# Charge_Controller.net
KiCad netlist of a schematic drawn in Altium Designer
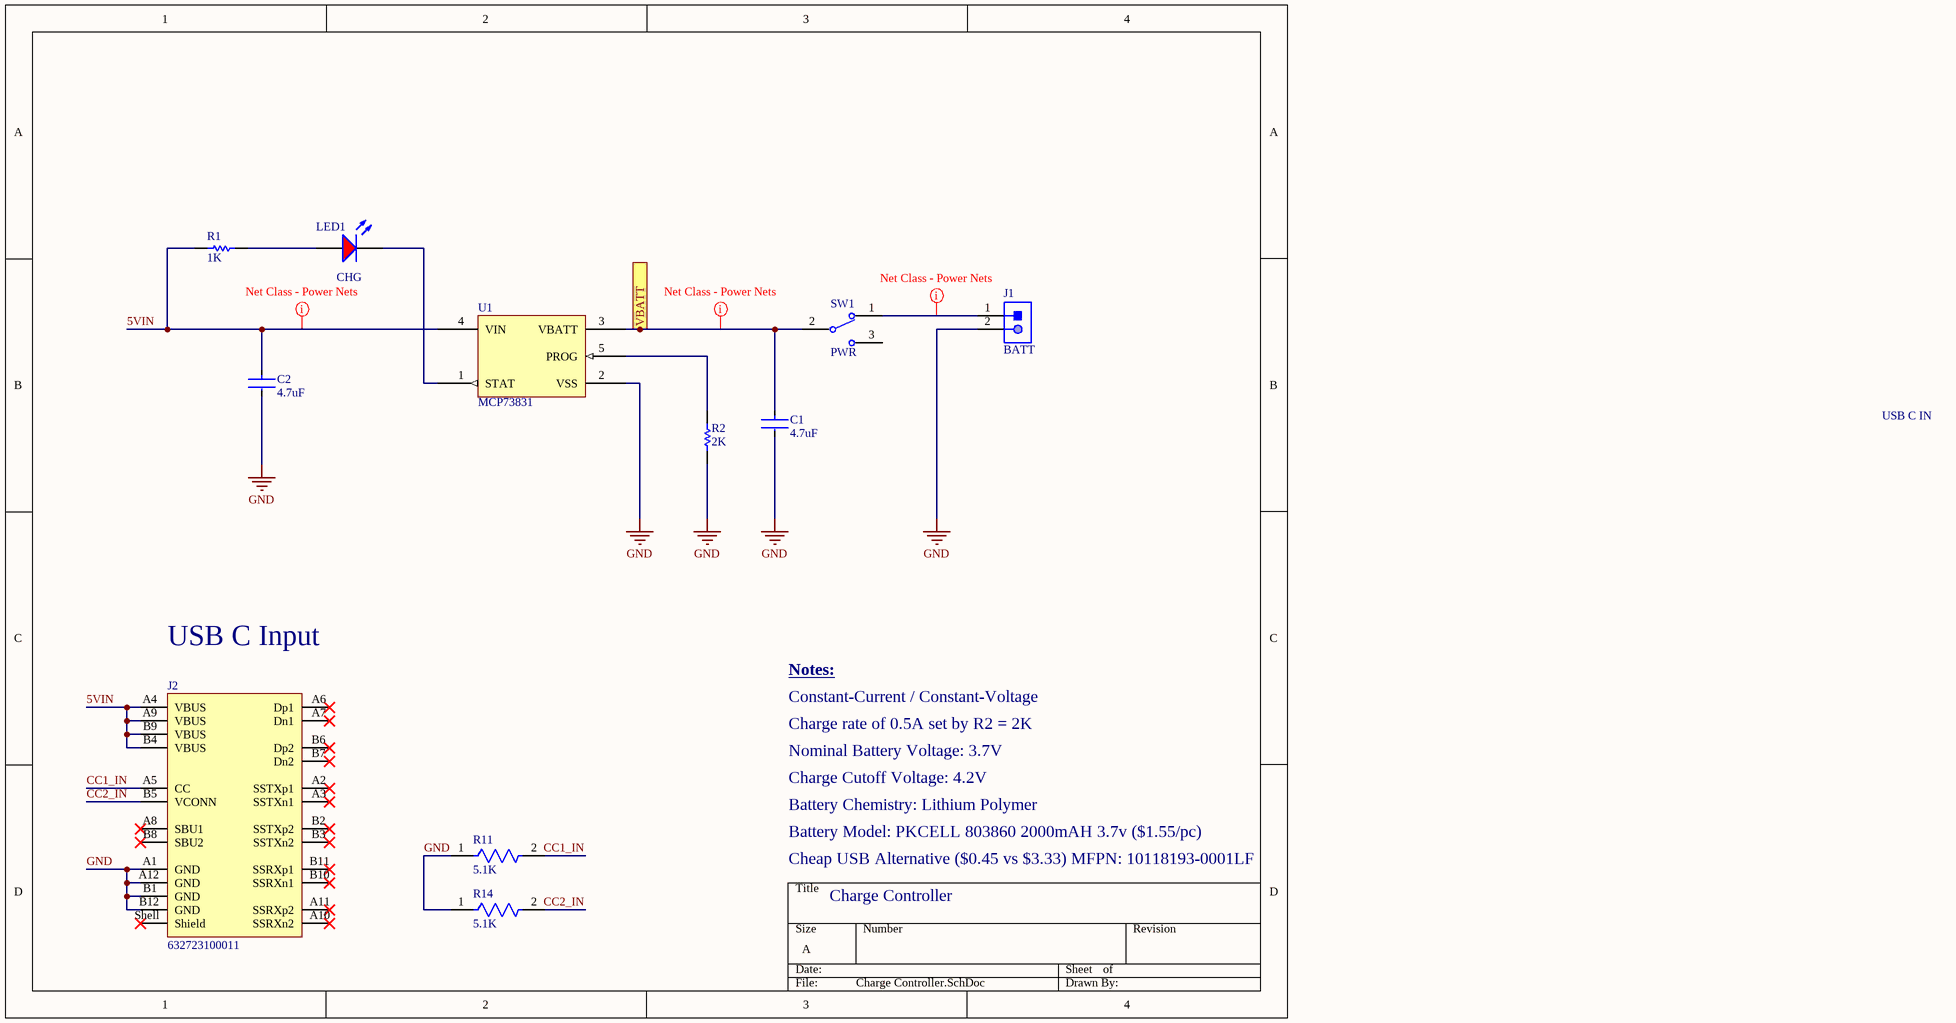
[diagram p0: Charge Controller.SchDoc]

(export (version "E")
  (design (tool "Eeschema 10.0.6"))
  (components
    (comp (ref "C1")
      (value "4.7uF")
      (footprint "FP-C0805C475K8PACTU-MFG")
      (description "CAP CER 4.7UF 10V X5R 0805")
      (fields (field (name "TOLERANCE") "10%") (field (name "VOLTAGE") "10V"))
      (libsource (lib "Altium Content Vault") (part "e9c51b7dd13d4faca003ae77663ab08"))
    )
    (comp (ref "C2")
      (value "4.7uF")
      (footprint "FP-C0805C475K8PACTU-MFG")
      (description "CAP CER 4.7UF 10V X5R 0805")
      (fields (field (name "TOLERANCE") "10%") (field (name "VOLTAGE") "10V"))
      (libsource (lib "Altium Content Vault") (part "e9c51b7dd13d4faca003ae77663ab08"))
    )
    (comp (ref "J1")
      (value "BATT")
      (footprint "JST-S2B-PH-K-S_V")
      (fields (field (name "TOLERANCE") "20%"))
      (libsource (lib "Altium Content Vault") (part "CN-1P-M-R2"))
    )
    (comp (ref "J2")
      (value "632723100011")
      (footprint "632723100011")
      (description "USB Connector, 24 Contact(s), Female, Right Angle, Solder and Surface Mount Terminal, Receptacle")
      (libsource (lib "Altium Content Vault") (part "USB 3.1_Type C_Receptacle_1 Port"))
    )
    (comp (ref "LED1")
      (value "CHG")
      (footprint "WL-SMCW_0805_150080xx75000")
      (description "LED Uni-Color Red 630nm 2-Pin Chip 0805(2012Metric) T/R")
      (libsource (lib "Altium Content Vault") (part "LED_Red_2A-1K"))
    )
    (comp (ref "R1")
      (value "1K")
      (footprint "RESC2013X60X35ML10T20")
      (description "Chip Resistor, 1 KOhm, +/- 1%, 125 mW, -55 to 155 degC, 0805 (2012 Metric), RoHS, Tape and Reel")
      (fields (field (name "TOLERANCE") "1%") (field (name "MANUFACTURER") "Yageo"))
      (libsource (lib "Altium Content Vault") (part "RES-2"))
    )
    (comp (ref "R2")
      (value "2K")
      (footprint "RESC2013X60X35ML10T20")
      (fields (field (name "MANUFACTURER") "Yageo") (field (name "PART NUMBER") "RC0805JR-072KL"))
      (libsource (lib "Altium Content Vault") (part "RES"))
    )
    (comp (ref "R11")
      (value "5.1K")
      (footprint "FP-CRCW0805-e3-MFG")
      (description "RES Thick Film, 5.1kΩ, 1%, 0.125W, 100ppm/°C, 0805")
      (fields (field (name "TOLERANCE") "1%"))
      (libsource (lib "Altium Content Vault") (part "1029c3af85768c4190bb7ad29bc67b5"))
    )
    (comp (ref "R14")
      (value "5.1K")
      (footprint "FP-CRCW0805-e3-MFG")
      (description "RES Thick Film, 5.1kΩ, 1%, 0.125W, 100ppm/°C, 0805")
      (fields (field (name "TOLERANCE") "1%"))
      (libsource (lib "Altium Content Vault") (part "1029c3af85768c4190bb7ad29bc67b5"))
    )
    (comp (ref "SW1")
      (value "PWR")
      (footprint "FP-JS102011JAQN-MFG")
      (description "Slide Switch SPDT Surface Mount, Right Angle")
      (fields (field (name "MANUFACTURER") "C&K"))
      (libsource (lib "Altium Content Vault") (part "3307bfe30257a22cc26f07bdba41a07"))
    )
    (comp (ref "U1")
      (value "MCP73831")
      (footprint "SOT95P280X145-5N")
      (description "MCP73831 Series Single-Cell Li-Ion/Li-Polymer Battery Charge Controller SOT-23-5")
      (fields
        (field (name "MANUFACTURER") "Microchip")
        (field (name "MANUFACTURER PART NUMBER") "MCP73831T-2ACI/OT")
      )
      (libsource (lib "CustomLib") (part "MCP73831"))
    )
  )
  (nets
    (net (code "1") (name "/5VIN") (class "Default")
      (node (ref "C2") (pin "1") (pinfunction "1_1") (pintype "passive"))
      (node (ref "J2") (pin "A4") (pinfunction "VBUS_A4") (pintype "passive"))
      (node (ref "J2") (pin "A9") (pinfunction "VBUS_A9") (pintype "passive"))
      (node (ref "J2") (pin "B4") (pinfunction "VBUS_B4") (pintype "passive"))
      (node (ref "J2") (pin "B9") (pinfunction "VBUS_B9") (pintype "passive"))
      (node (ref "R1") (pin "1") (pinfunction "1_1") (pintype "passive"))
      (node (ref "U1") (pin "4") (pinfunction "VIN_4") (pintype "power_in"))
    )
    (net (code "2") (name "/CC1_IN") (class "Default")
      (node (ref "J2") (pin "A5") (pinfunction "CC_A5") (pintype "passive"))
      (node (ref "R11") (pin "2") (pinfunction "2_2") (pintype "passive"))
    )
    (net (code "3") (name "/CC2_IN") (class "Default")
      (node (ref "J2") (pin "B5") (pinfunction "VCONN_B5") (pintype "passive"))
      (node (ref "R14") (pin "2") (pinfunction "2_2") (pintype "passive"))
    )
    (net (code "4") (name "/VBATT") (class "Default")
      (node (ref "C1") (pin "1") (pinfunction "1_1") (pintype "passive"))
      (node (ref "SW1") (pin "2") (pinfunction "C_2") (pintype "passive"))
      (node (ref "U1") (pin "3") (pinfunction "VBATT_3") (pintype "power_in"))
    )
    (net (code "5") (name "GND") (class "Default")
      (node (ref "C1") (pin "2") (pinfunction "2_2") (pintype "passive"))
      (node (ref "C2") (pin "2") (pinfunction "2_2") (pintype "passive"))
      (node (ref "J1") (pin "2") (pinfunction "2_2") (pintype "passive"))
      (node (ref "J2") (pin "A1") (pinfunction "GND_A1") (pintype "passive"))
      (node (ref "J2") (pin "A12") (pinfunction "GND_A12") (pintype "passive"))
      (node (ref "J2") (pin "B1") (pinfunction "GND_B1") (pintype "passive"))
      (node (ref "J2") (pin "B12") (pinfunction "GND_B12") (pintype "passive"))
      (node (ref "R11") (pin "1") (pinfunction "1_1") (pintype "passive"))
      (node (ref "R14") (pin "1") (pinfunction "1_1") (pintype "passive"))
      (node (ref "R2") (pin "1") (pinfunction "1_1") (pintype "passive"))
      (node (ref "U1") (pin "2") (pinfunction "VSS_2") (pintype "power_in"))
    )
    (net (code "6") (name "Net-(J1-Pad1)") (class "Default")
      (node (ref "J1") (pin "1") (pinfunction "1_1") (pintype "passive"))
      (node (ref "SW1") (pin "1") (pinfunction "1_1") (pintype "passive"))
    )
    (net (code "7") (name "Net-(LED1-A)") (class "Default")
      (node (ref "LED1") (pin "2") (pinfunction "A_2") (pintype "passive"))
      (node (ref "R1") (pin "2") (pinfunction "2_2") (pintype "passive"))
    )
    (net (code "8") (name "Net-(LED1-K)") (class "Default")
      (node (ref "LED1") (pin "1") (pinfunction "K_1") (pintype "passive"))
      (node (ref "U1") (pin "1") (pinfunction "STAT_1") (pintype "output"))
    )
    (net (code "9") (name "Net-(U1-PROG)") (class "Default")
      (node (ref "R2") (pin "2") (pinfunction "2_2") (pintype "passive"))
      (node (ref "U1") (pin "5") (pinfunction "PROG_5") (pintype "input"))
    )
    (net (code "10") (name "unconnected-(J2-Dn1-PadA7)") (class "Default")
      (node (ref "J2") (pin "A7") (pinfunction "Dn1_A7") (pintype "passive+no_connect"))
    )
    (net (code "11") (name "unconnected-(J2-Dn2-PadB7)") (class "Default")
      (node (ref "J2") (pin "B7") (pinfunction "Dn2_B7") (pintype "passive+no_connect"))
    )
    (net (code "12") (name "unconnected-(J2-Dp1-PadA6)") (class "Default")
      (node (ref "J2") (pin "A6") (pinfunction "Dp1_A6") (pintype "passive+no_connect"))
    )
    (net (code "13") (name "unconnected-(J2-Dp2-PadB6)") (class "Default")
      (node (ref "J2") (pin "B6") (pinfunction "Dp2_B6") (pintype "passive+no_connect"))
    )
    (net (code "14") (name "unconnected-(J2-SBU1-PadA8)") (class "Default")
      (node (ref "J2") (pin "A8") (pinfunction "SBU1_A8") (pintype "passive+no_connect"))
    )
    (net (code "15") (name "unconnected-(J2-SBU2-PadB8)") (class "Default")
      (node (ref "J2") (pin "B8") (pinfunction "SBU2_B8") (pintype "passive+no_connect"))
    )
    (net (code "16") (name "unconnected-(J2-SSRXn1-PadB10)") (class "Default")
      (node (ref "J2") (pin "B10") (pinfunction "SSRXn1_B10") (pintype "passive+no_connect"))
    )
    (net (code "17") (name "unconnected-(J2-SSRXn2-PadA10)") (class "Default")
      (node (ref "J2") (pin "A10") (pinfunction "SSRXn2_A10") (pintype "passive+no_connect"))
    )
    (net (code "18") (name "unconnected-(J2-SSRXp1-PadB11)") (class "Default")
      (node (ref "J2") (pin "B11") (pinfunction "SSRXp1_B11") (pintype "passive+no_connect"))
    )
    (net (code "19") (name "unconnected-(J2-SSRXp2-PadA11)") (class "Default")
      (node (ref "J2") (pin "A11") (pinfunction "SSRXp2_A11") (pintype "passive+no_connect"))
    )
    (net (code "20") (name "unconnected-(J2-SSTXn1-PadA3)") (class "Default")
      (node (ref "J2") (pin "A3") (pinfunction "SSTXn1_A3") (pintype "passive+no_connect"))
    )
    (net (code "21") (name "unconnected-(J2-SSTXn2-PadB3)") (class "Default")
      (node (ref "J2") (pin "B3") (pinfunction "SSTXn2_B3") (pintype "passive+no_connect"))
    )
    (net (code "22") (name "unconnected-(J2-SSTXp1-PadA2)") (class "Default")
      (node (ref "J2") (pin "A2") (pinfunction "SSTXp1_A2") (pintype "passive+no_connect"))
    )
    (net (code "23") (name "unconnected-(J2-SSTXp2-PadB2)") (class "Default")
      (node (ref "J2") (pin "B2") (pinfunction "SSTXp2_B2") (pintype "passive+no_connect"))
    )
    (net (code "24") (name "unconnected-(J2-Shield-PadShell)") (class "Default")
      (node (ref "J2") (pin "Shell") (pinfunction "Shield_Shell") (pintype "passive+no_connect"))
    )
    (net (code "25") (name "unconnected-(SW1-Pad3)") (class "Default")
      (node (ref "SW1") (pin "3") (pinfunction "3_3") (pintype "passive"))
    )
  )
)
